# 02_Power.net
KiCad netlist of a schematic drawn in Altium Designer
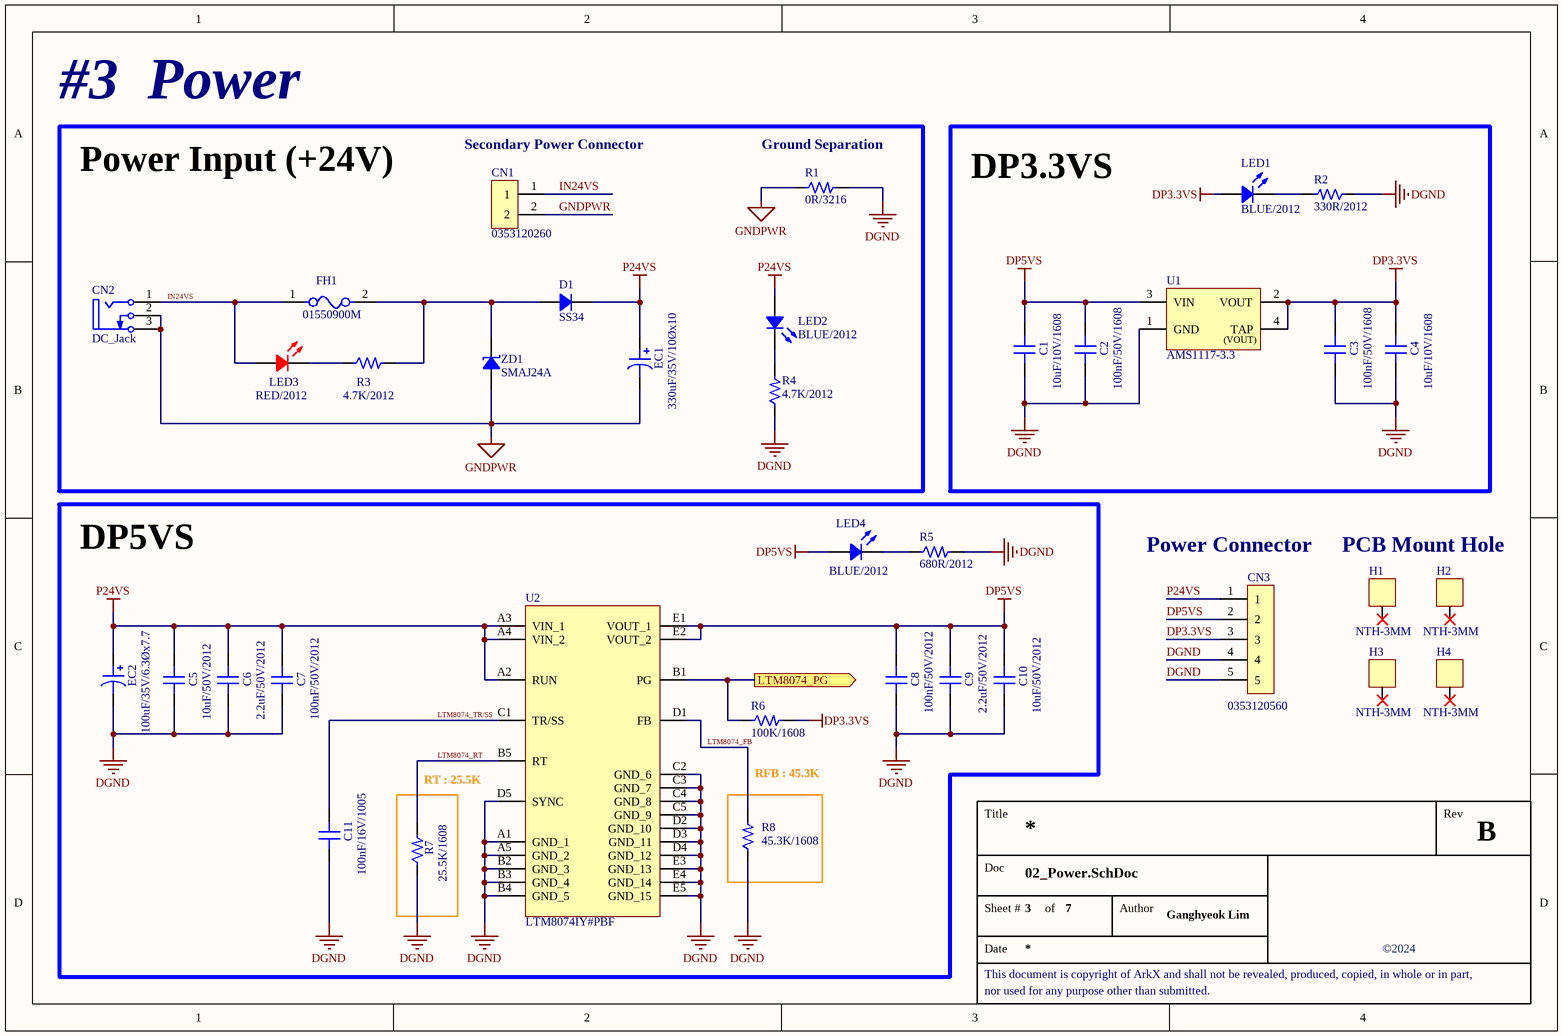
[diagram p0: 02_Power.SchDoc]

(export (version "E")
  (design (tool "Eeschema 10.0.6"))
  (components
    (comp (ref "C1")
      (value "10uF/10V/1608")
      (footprint "CAP 1608 (0603_INCH)")
      (description "Ceramic CAP_10uF/10V/1608")
      (fields (field (name "LCSC PART #") "C19702"))
      (libsource (lib "Arkx") (part "CAP_10uF/10V/1608"))
    )
    (comp (ref "C2")
      (value "100nF/50V/1608")
      (footprint "CAP 1608 (0603_INCH)")
      (description "Ceramic CAP_100nF/50V/1608")
      (fields (field (name "LCSC PART #") "C14663"))
      (libsource (lib "Arkx") (part "CAP_100nF/50V/1608"))
    )
    (comp (ref "C3")
      (value "100nF/50V/1608")
      (footprint "CAP 1608 (0603_INCH)")
      (description "Ceramic CAP_100nF/50V/1608")
      (fields (field (name "LCSC PART #") "C14663"))
      (libsource (lib "Arkx") (part "CAP_100nF/50V/1608"))
    )
    (comp (ref "C4")
      (value "10uF/10V/1608")
      (footprint "CAP 1608 (0603_INCH)")
      (description "Ceramic CAP_10uF/10V/1608")
      (fields (field (name "LCSC PART #") "C19702"))
      (libsource (lib "Arkx") (part "CAP_10uF/10V/1608"))
    )
    (comp (ref "C5")
      (value "10uF/50V/2012")
      (footprint "CAP 2012 (0805_INCH)")
      (description "Ceramic CAP_10uF/50V/2012")
      (fields (field (name "LCSC PART #") "C440198"))
      (libsource (lib "Arkx") (part "CAP_10uF/50V/2012"))
    )
    (comp (ref "C6")
      (value "2.2uF/50V/2012")
      (footprint "CAP 2012 (0805_INCH)")
      (description "Ceramic CAP_2.2uF/50V/2012")
      (fields (field (name "LCSC PART #") "C49217"))
      (libsource (lib "Arkx") (part "CAP_2.2uF/50V/2012"))
    )
    (comp (ref "C7")
      (value "100nF/50V/2012")
      (footprint "CAP 2012 (0805_INCH)")
      (description "Ceramic CAP_100nF/50V/2012")
      (fields (field (name "LCSC PART #") "C49678"))
      (libsource (lib "Arkx") (part "CAP_100nF/50V/2012"))
    )
    (comp (ref "C8")
      (value "100nF/50V/2012")
      (footprint "CAP 2012 (0805_INCH)")
      (description "Ceramic CAP_100nF/50V/2012")
      (fields (field (name "LCSC PART #") "C49678"))
      (libsource (lib "Arkx") (part "CAP_100nF/50V/2012"))
    )
    (comp (ref "C9")
      (value "2.2uF/50V/2012")
      (footprint "CAP 2012 (0805_INCH)")
      (description "Ceramic CAP_2.2uF/50V/2012")
      (fields (field (name "LCSC PART #") "C49217"))
      (libsource (lib "Arkx") (part "CAP_2.2uF/50V/2012"))
    )
    (comp (ref "C10")
      (value "10uF/50V/2012")
      (footprint "CAP 2012 (0805_INCH)")
      (description "Ceramic CAP_10uF/50V/2012")
      (fields (field (name "LCSC PART #") "C440198"))
      (libsource (lib "Arkx") (part "CAP_10uF/50V/2012"))
    )
    (comp (ref "C11")
      (value "100nF/16V/1005")
      (footprint "CAP 1005 (0402_INCH)")
      (description "Ceramic CAP_100nF/16V/1005")
      (fields (field (name "LCSC PART #") "C1525"))
      (libsource (lib "Arkx") (part "CAP_100nF/16V/1005"))
    )
    (comp (ref "CN1")
      (value "0353120260")
      (footprint "CON 0353120260 (MOLEX)")
      (description "CONN HEADER VERT 2POS 2.5MM")
      (libsource (lib "Arkx") (part "CON_0353120260"))
    )
    (comp (ref "CN2")
      (value "DC_Jack")
      (footprint "CON DC-Jack")
      (libsource (lib "Arkx") (part "CON_DC-Jack"))
    )
    (comp (ref "CN3")
      (value "0353120560")
      (footprint "CON 0353120560 (MOLEX)")
      (description "CONN HEADER VERT 5POS 2.5MM")
      (libsource (lib "Arkx") (part "CON_0353120560"))
    )
    (comp (ref "D1")
      (value "SS34")
      (footprint "DIO DO-214AC (SMA)")
      (description "DIODE SCHOTTKY 40V 3A SMC")
      (fields (field (name "LCSC PART #") "C8678"))
      (libsource (lib "Arkx") (part "DIO_SS34"))
    )
    (comp (ref "EC1")
      (value "330uF/35V/10Øx10")
      (footprint "CAP ALSMD 10.3MM H10.5MM LEADSPANMAX12MM")
      (description "Electrolytic CAP_330uF/35V/10Øx10")
      (fields (field (name "LCSC PART #") "C311621"))
      (libsource (lib "Arkx") (part "CAP_EC 330uF/35V/10Øx10"))
    )
    (comp (ref "EC2")
      (value "100uF/35V/6.3Øx7.7")
      (footprint "CAP ALSMD 6.6MM H7.7MM")
      (description "Eletrolytic CAP_100uF/35V/6.3Øx7.7")
      (fields (field (name "LCSC PART #") "C176666"))
      (libsource (lib "Arkx") (part "CAP_EC 100uF/35V/6.3Øx7.7"))
    )
    (comp (ref "FH1")
      (value "01550900M")
      (footprint "FUSE 01550900M_SMD(Hand_Solder)")
      (description "Fuse Block 10A 125V 1 Circuit Cartridge Surface Mount")
      (fields (field (name "LCSC PART #") "C108518"))
      (libsource (lib "Arkx") (part "FUSE_01550900M-SMD"))
    )
    (comp (ref "H1")
      (value "NTH-3MM")
      (footprint "HOLE NTH-3MM")
      (description "Non-Through Hole 3mm")
      (libsource (lib "Arkx") (part "HOLE_NTH-3MM"))
    )
    (comp (ref "H2")
      (value "NTH-3MM")
      (footprint "HOLE NTH-3MM")
      (description "Non-Through Hole 3mm")
      (libsource (lib "Arkx") (part "HOLE_NTH-3MM"))
    )
    (comp (ref "H3")
      (value "NTH-3MM")
      (footprint "HOLE NTH-3MM")
      (description "Non-Through Hole 3mm")
      (libsource (lib "Arkx") (part "HOLE_NTH-3MM"))
    )
    (comp (ref "H4")
      (value "NTH-3MM")
      (footprint "HOLE NTH-3MM")
      (description "Non-Through Hole 3mm")
      (libsource (lib "Arkx") (part "HOLE_NTH-3MM"))
    )
    (comp (ref "LED1")
      (value "BLUE/2012")
      (footprint "LED MHT170RGBCT (BLUE)")
      (fields (field (name "LCSC PART #") "C2962094"))
      (libsource (lib "Arkx") (part "LED_MHT170RGBCT(BLUE)"))
    )
    (comp (ref "LED2")
      (value "BLUE/2012")
      (footprint "LED MHT170RGBCT (BLUE)")
      (fields (field (name "LCSC PART #") "C2962094"))
      (libsource (lib "Arkx") (part "LED_MHT170RGBCT(BLUE)"))
    )
    (comp (ref "LED3")
      (value "RED/2012")
      (footprint "LED MHT170RGBCT (RED)")
      (fields (field (name "LCSC PART #") "C2962094"))
      (libsource (lib "Arkx") (part "LED_MHT170RGBCT(RED)"))
    )
    (comp (ref "LED4")
      (value "BLUE/2012")
      (footprint "LED MHT170RGBCT (BLUE)")
      (fields (field (name "LCSC PART #") "C2962094"))
      (libsource (lib "Arkx") (part "LED_MHT170RGBCT(BLUE)"))
    )
    (comp (ref "R1")
      (value "0R/3216")
      (footprint "RES 3216 (1206_inch)")
      (description "RES_0R/3216/0.25W")
      (fields (field (name "LCSC PART #") "C17888"))
      (libsource (lib "Arkx") (part "RES_0R/3216/0.25W"))
    )
    (comp (ref "R2")
      (value "330R/2012")
      (footprint "RES 2012 (0805_inch)")
      (description "RES_330R/2012/0.125W")
      (fields (field (name "LCSC PART #") "C17630"))
      (libsource (lib "Arkx") (part "RES_330R/2012/0.125W"))
    )
    (comp (ref "R3")
      (value "4.7K/2012")
      (footprint "RES 2012 (0805_inch)")
      (description "RES_4.7K/2012/0.125W")
      (fields (field (name "LCSC PART #") "C17673"))
      (libsource (lib "Arkx") (part "RES_4.7K/2012/0.125W"))
    )
    (comp (ref "R4")
      (value "4.7K/2012")
      (footprint "RES 2012 (0805_inch)")
      (description "RES_4.7K/2012/0.125W")
      (fields (field (name "LCSC PART #") "C17673"))
      (libsource (lib "Arkx") (part "RES_4.7K/2012/0.125W"))
    )
    (comp (ref "R5")
      (value "680R/2012")
      (footprint "RES 2012 (0805_inch)")
      (description "RES_680R/2012/0.125W")
      (fields (field (name "LCSC PART #") "C17798"))
      (libsource (lib "Arkx") (part "RES_680R/2012/0.125W"))
    )
    (comp (ref "R6")
      (value "100K/1608")
      (footprint "RES 1608 (0603_inch)")
      (description "RES_100K/1608/0.1W")
      (fields (field (name "LCSC PART #") "C25803"))
      (libsource (lib "Arkx") (part "RES_100K/1608/0.1W"))
    )
    (comp (ref "R7")
      (value "25.5K/1608")
      (footprint "RES 1608 (0603_inch)")
      (description "RES_25.5K/1608/0.1W")
      (fields (field (name "LCSC PART #") "C321813"))
      (libsource (lib "Arkx") (part "RES_25.5K/1608/0.1W"))
    )
    (comp (ref "R8")
      (value "45.3K/1608")
      (footprint "RES 1608 (0603_inch)")
      (description "RES_45.3K/1608/0.1W")
      (fields (field (name "LCSC PART #") "C304756"))
      (libsource (lib "Arkx") (part "RES_45.3K/1608/0.1W"))
    )
    (comp (ref "U1")
      (value "AMS1117-3.3")
      (footprint "SOT 223-3 (DIODES INCORPORATED)")
      (fields (field (name "LCSC PART #") "C6186"))
      (libsource (lib "Arkx") (part "IC_REG_AMS1117-3.3"))
    )
    (comp (ref "U2")
      (value "LTM8074IY#PBF")
      (footprint "IC_BGA-25")
      (description "1.2A, 40V DC/DC Buck Module Reg")
      (fields (field (name "LCSC PART #") "C690772"))
      (libsource (lib "Arkx") (part "IC_REG_LTM8074IY#PBF"))
    )
    (comp (ref "ZD1")
      (value "SMAJ24A")
      (footprint "DIO DO-214AC (SMA)")
      (description "Rectifier Diode")
      (fields (field (name "LCSC PART #") "C113962"))
      (libsource (lib "Arkx") (part "DIO_SMAJ24A"))
    )
  )
  (nets
    (net (code "1") (name "/IN24VS") (class "Default")
      (node (ref "CN1") (pin "1") (pinfunction "1_1") (pintype "passive"))
      (node (ref "CN2") (pin "1") (pinfunction "VCC_1") (pintype "power_in"))
      (node (ref "FH1") (pin "1") (pinfunction "1_1") (pintype "passive"))
      (node (ref "LED3") (pin "4") (pinfunction "Common_Anode_4") (pintype "passive"))
    )
    (net (code "2") (name "/LTM8074_FB") (class "Default")
      (node (ref "R8") (pin "2") (pinfunction "2_2") (pintype "passive"))
      (node (ref "U2") (pin "D1") (pinfunction "FB_D1") (pintype "passive"))
    )
    (net (code "3") (name "/LTM8074_PG") (class "Default")
      (node (ref "R6") (pin "1") (pinfunction "1_1") (pintype "passive"))
      (node (ref "U2") (pin "B1") (pinfunction "PG_B1") (pintype "passive"))
    )
    (net (code "4") (name "/LTM8074_RT") (class "Default")
      (node (ref "R7") (pin "2") (pinfunction "2_2") (pintype "passive"))
      (node (ref "U2") (pin "B5") (pinfunction "RT_B5") (pintype "passive"))
    )
    (net (code "5") (name "/LTM8074_TR{slash}SS") (class "Default")
      (node (ref "C11") (pin "2") (pinfunction "2_2") (pintype "passive"))
      (node (ref "U2") (pin "C1") (pinfunction "TR/SS_C1") (pintype "passive"))
    )
    (net (code "6") (name "DGND") (class "Default")
      (node (ref "C1") (pin "1") (pinfunction "1_1") (pintype "passive"))
      (node (ref "C10") (pin "1") (pinfunction "1_1") (pintype "passive"))
      (node (ref "C11") (pin "1") (pinfunction "1_1") (pintype "passive"))
      (node (ref "C2") (pin "1") (pinfunction "1_1") (pintype "passive"))
      (node (ref "C3") (pin "1") (pinfunction "1_1") (pintype "passive"))
      (node (ref "C4") (pin "1") (pinfunction "1_1") (pintype "passive"))
      (node (ref "C5") (pin "1") (pinfunction "1_1") (pintype "passive"))
      (node (ref "C6") (pin "1") (pinfunction "1_1") (pintype "passive"))
      (node (ref "C7") (pin "1") (pinfunction "1_1") (pintype "passive"))
      (node (ref "C8") (pin "1") (pinfunction "1_1") (pintype "passive"))
      (node (ref "C9") (pin "1") (pinfunction "1_1") (pintype "passive"))
      (node (ref "CN3") (pin "4") (pinfunction "4_4") (pintype "passive"))
      (node (ref "CN3") (pin "5") (pinfunction "5_5") (pintype "passive"))
      (node (ref "EC2") (pin "2") (pinfunction "2_2") (pintype "passive"))
      (node (ref "R1") (pin "2") (pinfunction "2_2") (pintype "passive"))
      (node (ref "R2") (pin "1") (pinfunction "1_1") (pintype "passive"))
      (node (ref "R4") (pin "1") (pinfunction "1_1") (pintype "passive"))
      (node (ref "R5") (pin "2") (pinfunction "2_2") (pintype "passive"))
      (node (ref "R7") (pin "1") (pinfunction "1_1") (pintype "passive"))
      (node (ref "R8") (pin "1") (pinfunction "1_1") (pintype "passive"))
      (node (ref "U1") (pin "1") (pinfunction "GND_1") (pintype "passive"))
      (node (ref "U2") (pin "A1") (pinfunction "GND_1_A1") (pintype "passive"))
      (node (ref "U2") (pin "A5") (pinfunction "GND_2_A5") (pintype "passive"))
      (node (ref "U2") (pin "B2") (pinfunction "GND_3_B2") (pintype "passive"))
      (node (ref "U2") (pin "B3") (pinfunction "GND_4_B3") (pintype "passive"))
      (node (ref "U2") (pin "B4") (pinfunction "GND_5_B4") (pintype "passive"))
      (node (ref "U2") (pin "C2") (pinfunction "GND_6_C2") (pintype "passive"))
      (node (ref "U2") (pin "C3") (pinfunction "GND_7_C3") (pintype "passive"))
      (node (ref "U2") (pin "C4") (pinfunction "GND_8_C4") (pintype "passive"))
      (node (ref "U2") (pin "C5") (pinfunction "GND_9_C5") (pintype "passive"))
      (node (ref "U2") (pin "D2") (pinfunction "GND_10_D2") (pintype "passive"))
      (node (ref "U2") (pin "D3") (pinfunction "GND_11_D3") (pintype "passive"))
      (node (ref "U2") (pin "D4") (pinfunction "GND_12_D4") (pintype "passive"))
      (node (ref "U2") (pin "D5") (pinfunction "SYNC_D5") (pintype "passive"))
      (node (ref "U2") (pin "E3") (pinfunction "GND_13_E3") (pintype "passive"))
      (node (ref "U2") (pin "E4") (pinfunction "GND_14_E4") (pintype "passive"))
      (node (ref "U2") (pin "E5") (pinfunction "GND_15_E5") (pintype "passive"))
    )
    (net (code "7") (name "DP3.3VS") (class "Default")
      (node (ref "C3") (pin "2") (pinfunction "2_2") (pintype "passive"))
      (node (ref "C4") (pin "2") (pinfunction "2_2") (pintype "passive"))
      (node (ref "CN3") (pin "3") (pinfunction "3_3") (pintype "passive"))
      (node (ref "LED1") (pin "4") (pinfunction "Common_Anode_4") (pintype "passive"))
      (node (ref "R6") (pin "2") (pinfunction "2_2") (pintype "passive"))
      (node (ref "U1") (pin "2") (pinfunction "VOUT_2") (pintype "passive"))
      (node (ref "U1") (pin "4") (pinfunction "TAP_4") (pintype "passive"))
    )
    (net (code "8") (name "DP5VS") (class "Default")
      (node (ref "C1") (pin "2") (pinfunction "2_2") (pintype "passive"))
      (node (ref "C10") (pin "2") (pinfunction "2_2") (pintype "passive"))
      (node (ref "C2") (pin "2") (pinfunction "2_2") (pintype "passive"))
      (node (ref "C8") (pin "2") (pinfunction "2_2") (pintype "passive"))
      (node (ref "C9") (pin "2") (pinfunction "2_2") (pintype "passive"))
      (node (ref "CN3") (pin "2") (pinfunction "2_2") (pintype "passive"))
      (node (ref "LED4") (pin "4") (pinfunction "Common_Anode_4") (pintype "passive"))
      (node (ref "U1") (pin "3") (pinfunction "VIN_3") (pintype "passive"))
      (node (ref "U2") (pin "E1") (pinfunction "VOUT_1_E1") (pintype "passive"))
      (node (ref "U2") (pin "E2") (pinfunction "VOUT_2_E2") (pintype "passive"))
    )
    (net (code "9") (name "GNDPWR") (class "Default")
      (node (ref "CN1") (pin "2") (pinfunction "2_2") (pintype "passive"))
      (node (ref "CN2") (pin "2") (pinfunction "GND_2") (pintype "power_in"))
      (node (ref "CN2") (pin "3") (pinfunction "GND_3") (pintype "power_in"))
      (node (ref "EC1") (pin "2") (pinfunction "2_2") (pintype "passive"))
      (node (ref "R1") (pin "1") (pinfunction "1_1") (pintype "passive"))
      (node (ref "ZD1") (pin "1") (pinfunction "1_1") (pintype "passive"))
    )
    (net (code "10") (name "Net-(D1-Pad1)") (class "Default")
      (node (ref "D1") (pin "1") (pinfunction "1_1") (pintype "passive"))
      (node (ref "FH1") (pin "2") (pinfunction "2_2") (pintype "passive"))
      (node (ref "R3") (pin "2") (pinfunction "2_2") (pintype "passive"))
      (node (ref "ZD1") (pin "2") (pinfunction "2_2") (pintype "passive"))
    )
    (net (code "11") (name "Net-(LED1-BLUE)") (class "Default")
      (node (ref "LED1") (pin "3") (pinfunction "BLUE_3") (pintype "passive"))
      (node (ref "R2") (pin "2") (pinfunction "2_2") (pintype "passive"))
    )
    (net (code "12") (name "Net-(LED2-BLUE)") (class "Default")
      (node (ref "LED2") (pin "3") (pinfunction "BLUE_3") (pintype "passive"))
      (node (ref "R4") (pin "2") (pinfunction "2_2") (pintype "passive"))
    )
    (net (code "13") (name "Net-(LED3-RED)") (class "Default")
      (node (ref "LED3") (pin "1") (pinfunction "RED_1") (pintype "passive"))
      (node (ref "R3") (pin "1") (pinfunction "1_1") (pintype "passive"))
    )
    (net (code "14") (name "Net-(LED4-BLUE)") (class "Default")
      (node (ref "LED4") (pin "3") (pinfunction "BLUE_3") (pintype "passive"))
      (node (ref "R5") (pin "1") (pinfunction "1_1") (pintype "passive"))
    )
    (net (code "15") (name "P24VS") (class "Default")
      (node (ref "C5") (pin "2") (pinfunction "2_2") (pintype "passive"))
      (node (ref "C6") (pin "2") (pinfunction "2_2") (pintype "passive"))
      (node (ref "C7") (pin "2") (pinfunction "2_2") (pintype "passive"))
      (node (ref "CN3") (pin "1") (pinfunction "1_1") (pintype "passive"))
      (node (ref "D1") (pin "2") (pinfunction "2_2") (pintype "passive"))
      (node (ref "EC1") (pin "1") (pinfunction "1_1") (pintype "passive"))
      (node (ref "EC2") (pin "1") (pinfunction "1_1") (pintype "passive"))
      (node (ref "LED2") (pin "4") (pinfunction "Common_Anode_4") (pintype "passive"))
      (node (ref "U2") (pin "A2") (pinfunction "RUN_A2") (pintype "passive"))
      (node (ref "U2") (pin "A3") (pinfunction "VIN_1_A3") (pintype "passive"))
      (node (ref "U2") (pin "A4") (pinfunction "VIN_2_A4") (pintype "passive"))
    )
    (net (code "16") (name "unconnected-(H1-Pad1)") (class "Default")
      (node (ref "H1") (pin "1") (pinfunction "1_1") (pintype "passive+no_connect"))
    )
    (net (code "17") (name "unconnected-(H2-Pad1)") (class "Default")
      (node (ref "H2") (pin "1") (pinfunction "1_1") (pintype "passive+no_connect"))
    )
    (net (code "18") (name "unconnected-(H3-Pad1)") (class "Default")
      (node (ref "H3") (pin "1") (pinfunction "1_1") (pintype "passive+no_connect"))
    )
    (net (code "19") (name "unconnected-(H4-Pad1)") (class "Default")
      (node (ref "H4") (pin "1") (pinfunction "1_1") (pintype "passive+no_connect"))
    )
  )
)
